# STM32_microcontroller_IOs.net
KiCad netlist of a schematic drawn in Altium Designer
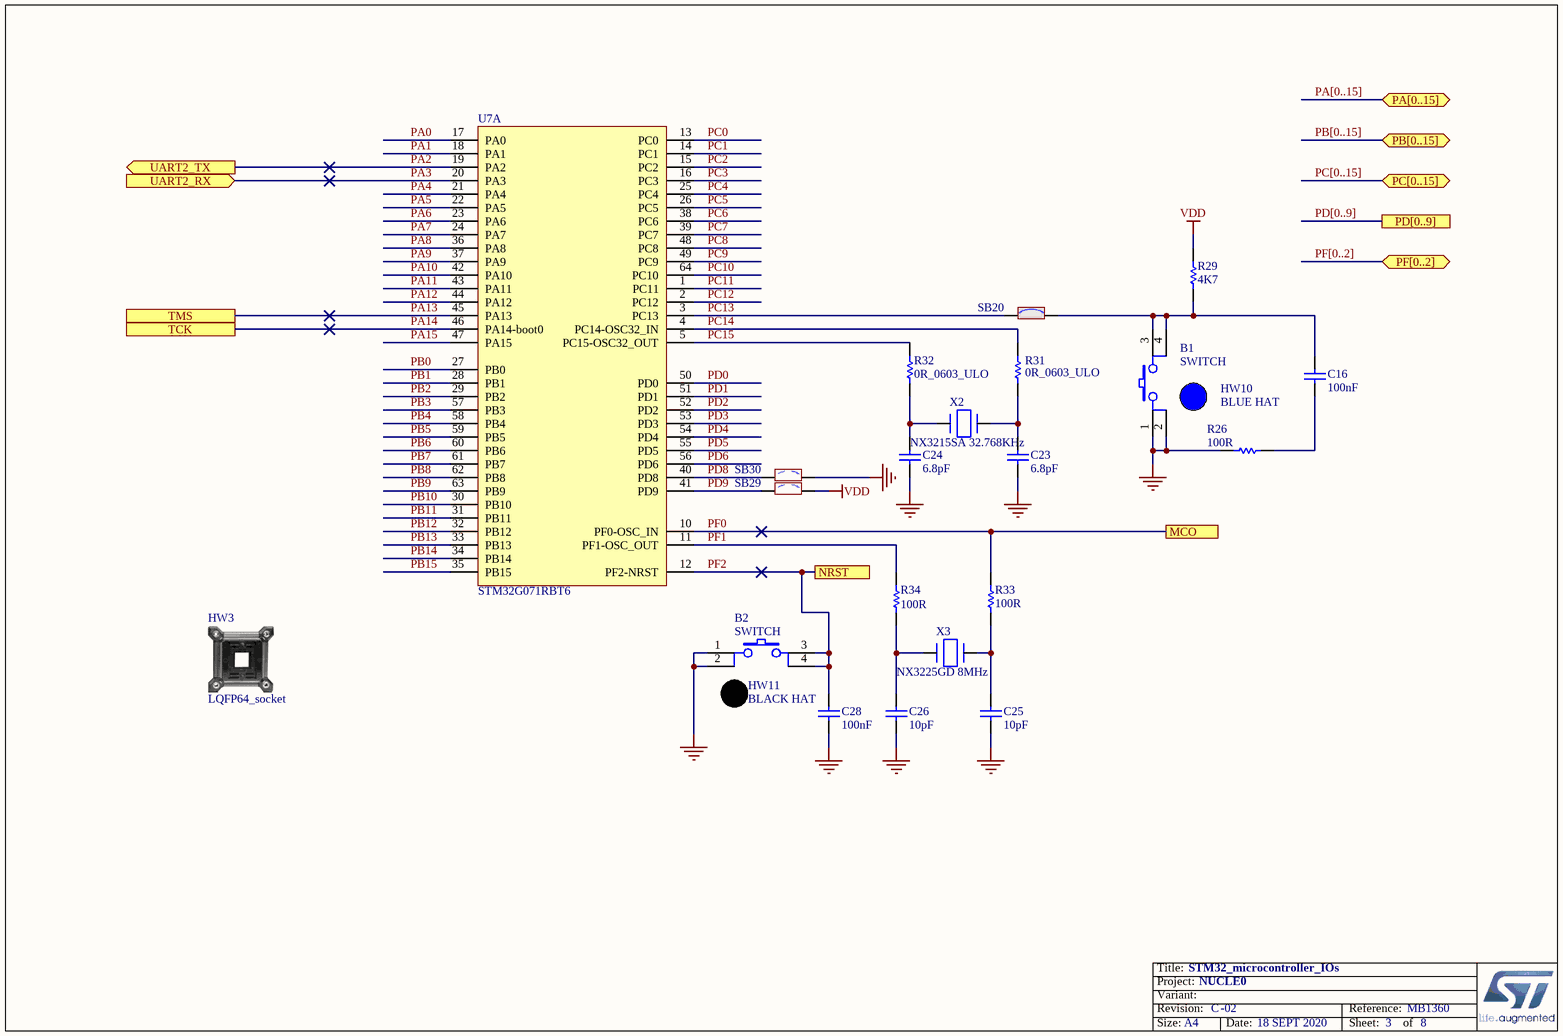
[diagram p0: STM32_microcontroller_IOs.SchDoc]

(export (version "E")
  (design (tool "Eeschema 10.0.6"))
  (components
    (comp (ref "B1")
      (value "SWITCH")
      (footprint "SWI_WEALTHMETAL_TD-0341_4P_BLUE")
      (description "Non-Open Push-Button 0.1A 24V")
      (fields
        (field (name "INTERNAL_PART_NUMBER") "MCD-00002")
        (field (name "MANUFACTURER_PART_NUMBER") "TD-0341")
        (field (name "PROVIDED_BY") "SUBCO")
      )
      (libsource (lib "MCD_PARTS_database") (part "SW-PUSH-CMS"))
    )
    (comp (ref "B2")
      (value "SWITCH")
      (footprint "SWI_WEALTHMETAL_TD-0341_4P_BLACK")
      (description "Non-Open Push-Button 0.1A 24V BLACK")
      (fields
        (field (name "INTERNAL_PART_NUMBER") "MCD-00001")
        (field (name "MANUFACTURER_PART_NUMBER") "TD-0341")
        (field (name "PROVIDED_BY") "SUBCO")
      )
      (libsource (lib "MCD_PARTS_database") (part "SW-PUSH-CMS"))
    )
    (comp (ref "C16")
      (value "100nF")
      (footprint "C0603")
      (description "Capacitor, MLCC, 100nF, 16V, X7R, 10%, 0603, T=0,8mm")
      (fields
        (field (name "INTERNAL_PART_NUMBER") "MCD-00211")
        (field (name "MANUFACTURER_PART_NUMBER") "CC0603KRX7R7BB104")
        (field (name "PROVIDED_BY") "SUBCO")
      )
      (libsource (lib "MCD_PARTS_database") (part "Capacitor"))
    )
    (comp (ref "C23")
      (value "6.8pF")
      (footprint "C0603")
      (description "Capacitor, MLCC, 6.8pF, 50V, NPO, -/+0.25pF, 0603, T=0,8mm")
      (fields (field (name "INTERNAL_PART_NUMBER") "MCD-00650") (field (name "MANUFACTURER") "YAGEO"))
      (libsource (lib "MCD_PARTS_database") (part "Capacitor"))
    )
    (comp (ref "C24")
      (value "6.8pF")
      (footprint "C0603")
      (description "Capacitor, MLCC, 6.8pF, 50V, NPO, -/+0.25pF, 0603, T=0,8mm")
      (fields (field (name "INTERNAL_PART_NUMBER") "MCD-00650") (field (name "MANUFACTURER") "YAGEO"))
      (libsource (lib "MCD_PARTS_database") (part "Capacitor"))
    )
    (comp (ref "C25")
      (value "10pF")
      (footprint "C0603")
      (description "Capacitor, MLCC, 10pF, 50V, NPO, 5%, 0603, T=0,8mm")
      (fields
        (field (name "INTERNAL_PART_NUMBER") "MCD-00637")
        (field (name "MANUFACTURER_PART_NUMBER") "CC0603JRNPO9BN100")
        (field (name "PROVIDED_BY") "SUBCO")
      )
      (libsource (lib "MCD_PARTS_database") (part "Capacitor"))
    )
    (comp (ref "C26")
      (value "10pF")
      (footprint "C0603")
      (description "Capacitor, MLCC, 10pF, 50V, NPO, 5%, 0603, T=0,8mm")
      (fields
        (field (name "INTERNAL_PART_NUMBER") "MCD-00637")
        (field (name "MANUFACTURER_PART_NUMBER") "CC0603JRNPO9BN100")
        (field (name "PROVIDED_BY") "SUBCO")
      )
      (libsource (lib "MCD_PARTS_database") (part "Capacitor"))
    )
    (comp (ref "C28")
      (value "100nF")
      (footprint "C0603")
      (description "Capacitor, MLCC, 100nF, 16V, X7R, 10%, 0603, T=0,8mm")
      (fields
        (field (name "INTERNAL_PART_NUMBER") "MCD-00211")
        (field (name "MANUFACTURER_PART_NUMBER") "CC0603KRX7R7BB104")
        (field (name "PROVIDED_BY") "SUBCO")
      )
      (libsource (lib "MCD_PARTS_database") (part "Capacitor"))
    )
    (comp (ref "HW3")
      (value "LQFP64_socket")
      (description "Yamaichi socket for LQFP64, with positioning pins.")
      (fields
        (field (name "INTERNAL_PART_NUMBER") "MCD-01253")
        (field (name "MANUFACTURER_PART_NUMBER") "IC149-064-169-B5")
        (field (name "PROVIDED_BY") "SUBCO")
      )
      (libsource (lib "MCD_PARTS_database") (part "SOCKET_LQFP64"))
    )
    (comp (ref "HW10")
      (value "BLUE HAT")
      (description "Blue Hat for switch TD0341X-G01-BLU")
      (fields
        (field (name "INTERNAL_PART_NUMBER") "MCD-00634")
        (field (name "MANUFACTURER_PART_NUMBER") "988.16.09.3.00002_SH-517")
        (field (name "PROVIDED_BY") "SUBCO")
      )
      (libsource (lib "MCD_PARTS_database") (part "BUTTON_HAT_BLUE"))
    )
    (comp (ref "HW11")
      (value "BLACK HAT")
      (description "Black Hat for switch TD0341X-G01-BLA")
      (fields
        (field (name "INTERNAL_PART_NUMBER") "MCD-00635")
        (field (name "MANUFACTURER_PART_NUMBER") "988.16.09.3.00003_SH-517")
        (field (name "PROVIDED_BY") "SUBCO")
      )
      (libsource (lib "MCD_PARTS_database") (part "BUTTON_HAT_BLACK"))
    )
    (comp (ref "R26")
      (value "100R")
      (footprint "R0603")
      (description "Resistor,100R,0603,1%,1/10W")
      (fields
        (field (name "INTERNAL_PART_NUMBER") "MCD-00224")
        (field (name "MANUFACTURER_PART_NUMBER") "RC0603FR-07100RL")
        (field (name "PROVIDED_BY") "SUBCO")
      )
      (libsource (lib "MCD_PARTS_database") (part "Resistor"))
    )
    (comp (ref "R29")
      (value "4K7")
      (footprint "R0603")
      (description "Resistor,4K7,0603,1%,1/10W")
      (fields
        (field (name "INTERNAL_PART_NUMBER") "MCD-00219")
        (field (name "MANUFACTURER_PART_NUMBER") "RC0603FR-074K7L")
        (field (name "PROVIDED_BY") "SUBCO")
      )
      (libsource (lib "MCD_PARTS_database") (part "Resistor"))
    )
    (comp (ref "R31")
      (value "0R_0603_ULO")
      (footprint "R0603")
      (description "Resistor,0R,0603,ULO")
      (fields
        (field (name "INTERNAL_PART_NUMBER") "MCD-00181")
        (field (name "MANUFACTURER_PART_NUMBER") "PMR03EZPJ000")
        (field (name "PROVIDED_BY") "SUBCO")
      )
      (libsource (lib "MCD_PARTS_database") (part "Resistor"))
    )
    (comp (ref "R32")
      (value "0R_0603_ULO")
      (footprint "R0603")
      (description "Resistor,0R,0603,ULO")
      (fields
        (field (name "INTERNAL_PART_NUMBER") "MCD-00181")
        (field (name "MANUFACTURER_PART_NUMBER") "PMR03EZPJ000")
        (field (name "PROVIDED_BY") "SUBCO")
      )
      (libsource (lib "MCD_PARTS_database") (part "Resistor"))
    )
    (comp (ref "R33")
      (value "100R")
      (footprint "R0603")
      (description "Resistor,100R,0603,1%,1/10W")
      (fields
        (field (name "INTERNAL_PART_NUMBER") "MCD-00224")
        (field (name "MANUFACTURER_PART_NUMBER") "RC0603FR-07100RL")
        (field (name "PROVIDED_BY") "SUBCO")
      )
      (libsource (lib "MCD_PARTS_database") (part "Resistor"))
    )
    (comp (ref "R34")
      (value "100R")
      (footprint "R0603")
      (description "Resistor,100R,0603,1%,1/10W")
      (fields
        (field (name "INTERNAL_PART_NUMBER") "MCD-00224")
        (field (name "MANUFACTURER_PART_NUMBER") "RC0603FR-07100RL")
        (field (name "PROVIDED_BY") "SUBCO")
      )
      (libsource (lib "MCD_PARTS_database") (part "Resistor"))
    )
    (comp (ref "SB20")
      (value "SB_ON")
      (footprint "SOLDER-BRIDGE_R0603-0R")
      (description "Solder Bridge ON")
      (fields
        (field (name "INTERNAL_PART_NUMBER") "MCD-00071")
        (field (name "MANUFACTURER_PART_NUMBER") "RC0603JR-070RL")
        (field (name "PROVIDED_BY") "SUBCO")
      )
      (libsource (lib "MCD_PARTS_database") (part "SB_ON"))
    )
    (comp (ref "SB29")
      (value "SB_OFF")
      (footprint "SOLDER-BRIDGE_R0603-0R")
      (description "Solder Bridge OFF")
      (fields
        (field (name "INTERNAL_PART_NUMBER") "MCD-00072")
        (field (name "MANUFACTURER_PART_NUMBER") "RC0603JR-070RL")
        (field (name "PROVIDED_BY") "SUBCO")
      )
      (libsource (lib "MCD_PARTS_database") (part "SB_OFF"))
    )
    (comp (ref "SB30")
      (value "SB_OFF")
      (footprint "SOLDER-BRIDGE_R0603-0R")
      (description "Solder Bridge OFF")
      (fields
        (field (name "INTERNAL_PART_NUMBER") "MCD-00072")
        (field (name "MANUFACTURER_PART_NUMBER") "RC0603JR-070RL")
        (field (name "PROVIDED_BY") "SUBCO")
      )
      (libsource (lib "MCD_PARTS_database") (part "SB_OFF"))
    )
    (comp (ref "U7")
      (value "STM32G071RBT6")
      (footprint "ICC_LQFP64_10X10_P050_SOCKET_YAMAICHI_IC149-064-069-B5")
      (fields
        (field (name "INTERNAL_PART_NUMBER") "MCD-00662")
        (field (name "MANUFACTURER") "STMICROELECTRONICS")
        (field (name "BMS_PART_NUMBER") "9175318")
        (field (name "PROVIDED_BY") "SUBCO with ST control")
      )
      (libsource (lib "MCD_PARTS_database") (part "STM32G071RBT6"))
    )
    (comp (ref "X2")
      (value "NX3215SA 32.768KHz")
      (footprint "CRY_NX3215SA_2P")
      (description "Crystal 32.768kHz, 6pF, +-20ppm, 50Kohms max, SMD")
      (fields
        (field (name "INTERNAL_PART_NUMBER") "MCD-00091")
        (field (name "MANUFACTURER_PART_NUMBER") "NX3215SA 32.768KHz EXS00A-MU00525")
        (field (name "PROVIDED_BY") "SUBCO")
      )
      (libsource (lib "MCD_PARTS_database") (part "XTAL_2_PINS"))
    )
    (comp (ref "X3")
      (value "NX3225GD 8MHz")
      (footprint "CRY_NX3225GD_2P")
      (description "Crystal 8MHz, 8pF, +-20ppm, 500ohms max,  SMD")
      (fields
        (field (name "INTERNAL_PART_NUMBER") "MCD-00092")
        (field (name "MANUFACTURER_PART_NUMBER") "NX3225GD 8MHz EXS00A-CG04874")
        (field (name "PROVIDED_BY") "SUBCO")
      )
      (libsource (lib "MCD_PARTS_database") (part "XTAL_2_PINS"))
    )
  )
  (nets
    (net (code "2") (name "/PA0") (class "Default")
      (node (ref "U7") (pin "17") (pinfunction "PA0_17") (pintype "passive"))
    )
    (net (code "3") (name "/PA1") (class "Default")
      (node (ref "U7") (pin "18") (pinfunction "PA1_18") (pintype "passive"))
    )
    (net (code "4") (name "/PA2") (class "Default")
      (node (ref "U7") (pin "19") (pinfunction "PA2_19") (pintype "passive"))
    )
    (net (code "5") (name "/PA3") (class "Default")
      (node (ref "U7") (pin "20") (pinfunction "PA3_20") (pintype "passive"))
    )
    (net (code "6") (name "/PA4") (class "Default")
      (node (ref "U7") (pin "21") (pinfunction "PA4_21") (pintype "passive"))
    )
    (net (code "7") (name "/PA5") (class "Default")
      (node (ref "U7") (pin "22") (pinfunction "PA5_22") (pintype "passive"))
    )
    (net (code "8") (name "/PA6") (class "Default")
      (node (ref "U7") (pin "23") (pinfunction "PA6_23") (pintype "passive"))
    )
    (net (code "9") (name "/PA7") (class "Default")
      (node (ref "U7") (pin "24") (pinfunction "PA7_24") (pintype "passive"))
    )
    (net (code "10") (name "/PA8") (class "Default")
      (node (ref "U7") (pin "36") (pinfunction "PA8_36") (pintype "passive"))
    )
    (net (code "11") (name "/PA9") (class "Default")
      (node (ref "U7") (pin "37") (pinfunction "PA9_37") (pintype "passive"))
    )
    (net (code "12") (name "/PA10") (class "Default")
      (node (ref "U7") (pin "42") (pinfunction "PA10_42") (pintype "passive"))
    )
    (net (code "13") (name "/PA11") (class "Default")
      (node (ref "U7") (pin "43") (pinfunction "PA11_43") (pintype "passive"))
    )
    (net (code "14") (name "/PA12") (class "Default")
      (node (ref "U7") (pin "44") (pinfunction "PA12_44") (pintype "passive"))
    )
    (net (code "15") (name "/PA13") (class "Default")
      (node (ref "U7") (pin "45") (pinfunction "PA13_45") (pintype "passive"))
    )
    (net (code "16") (name "/PA14") (class "Default")
      (node (ref "U7") (pin "46") (pinfunction "PA14-boot0_46") (pintype "passive"))
    )
    (net (code "17") (name "/PA15") (class "Default")
      (node (ref "U7") (pin "47") (pinfunction "PA15_47") (pintype "passive"))
    )
    (net (code "19") (name "/PB0") (class "Default")
      (node (ref "U7") (pin "27") (pinfunction "PB0_27") (pintype "passive"))
    )
    (net (code "20") (name "/PB1") (class "Default")
      (node (ref "U7") (pin "28") (pinfunction "PB1_28") (pintype "passive"))
    )
    (net (code "21") (name "/PB2") (class "Default")
      (node (ref "U7") (pin "29") (pinfunction "PB2_29") (pintype "passive"))
    )
    (net (code "22") (name "/PB3") (class "Default")
      (node (ref "U7") (pin "57") (pinfunction "PB3_57") (pintype "passive"))
    )
    (net (code "23") (name "/PB4") (class "Default")
      (node (ref "U7") (pin "58") (pinfunction "PB4_58") (pintype "passive"))
    )
    (net (code "24") (name "/PB5") (class "Default")
      (node (ref "U7") (pin "59") (pinfunction "PB5_59") (pintype "passive"))
    )
    (net (code "25") (name "/PB6") (class "Default")
      (node (ref "U7") (pin "60") (pinfunction "PB6_60") (pintype "passive"))
    )
    (net (code "26") (name "/PB7") (class "Default")
      (node (ref "U7") (pin "61") (pinfunction "PB7_61") (pintype "passive"))
    )
    (net (code "27") (name "/PB8") (class "Default")
      (node (ref "U7") (pin "62") (pinfunction "PB8_62") (pintype "passive"))
    )
    (net (code "28") (name "/PB9") (class "Default")
      (node (ref "U7") (pin "63") (pinfunction "PB9_63") (pintype "passive"))
    )
    (net (code "29") (name "/PB10") (class "Default")
      (node (ref "U7") (pin "30") (pinfunction "PB10_30") (pintype "passive"))
    )
    (net (code "30") (name "/PB11") (class "Default")
      (node (ref "U7") (pin "31") (pinfunction "PB11_31") (pintype "passive"))
    )
    (net (code "31") (name "/PB12") (class "Default")
      (node (ref "U7") (pin "32") (pinfunction "PB12_32") (pintype "passive"))
    )
    (net (code "32") (name "/PB13") (class "Default")
      (node (ref "U7") (pin "33") (pinfunction "PB13_33") (pintype "passive"))
    )
    (net (code "33") (name "/PB14") (class "Default")
      (node (ref "U7") (pin "34") (pinfunction "PB14_34") (pintype "passive"))
    )
    (net (code "34") (name "/PB15") (class "Default")
      (node (ref "U7") (pin "35") (pinfunction "PB15_35") (pintype "passive"))
    )
    (net (code "36") (name "/PC0") (class "Default")
      (node (ref "U7") (pin "13") (pinfunction "PC0_13") (pintype "passive"))
    )
    (net (code "37") (name "/PC1") (class "Default")
      (node (ref "U7") (pin "14") (pinfunction "PC1_14") (pintype "passive"))
    )
    (net (code "38") (name "/PC2") (class "Default")
      (node (ref "U7") (pin "15") (pinfunction "PC2_15") (pintype "passive"))
    )
    (net (code "39") (name "/PC3") (class "Default")
      (node (ref "U7") (pin "16") (pinfunction "PC3_16") (pintype "passive"))
    )
    (net (code "40") (name "/PC4") (class "Default")
      (node (ref "U7") (pin "25") (pinfunction "PC4_25") (pintype "passive"))
    )
    (net (code "41") (name "/PC5") (class "Default")
      (node (ref "U7") (pin "26") (pinfunction "PC5_26") (pintype "passive"))
    )
    (net (code "42") (name "/PC6") (class "Default")
      (node (ref "U7") (pin "38") (pinfunction "PC6_38") (pintype "passive"))
    )
    (net (code "43") (name "/PC7") (class "Default")
      (node (ref "U7") (pin "39") (pinfunction "PC7_39") (pintype "passive"))
    )
    (net (code "44") (name "/PC8") (class "Default")
      (node (ref "U7") (pin "48") (pinfunction "PC8_48") (pintype "passive"))
    )
    (net (code "45") (name "/PC9") (class "Default")
      (node (ref "U7") (pin "49") (pinfunction "PC9_49") (pintype "passive"))
    )
    (net (code "46") (name "/PC10") (class "Default")
      (node (ref "U7") (pin "64") (pinfunction "PC10_64") (pintype "passive"))
    )
    (net (code "47") (name "/PC11") (class "Default")
      (node (ref "U7") (pin "1") (pinfunction "PC11_1") (pintype "passive"))
    )
    (net (code "48") (name "/PC12") (class "Default")
      (node (ref "U7") (pin "2") (pinfunction "PC12_2") (pintype "passive"))
    )
    (net (code "49") (name "/PC13") (class "Default")
      (node (ref "SB20") (pin "1") (pinfunction "1_1") (pintype "passive"))
      (node (ref "U7") (pin "3") (pinfunction "PC13_3") (pintype "passive"))
    )
    (net (code "50") (name "/PC14") (class "Default")
      (node (ref "R31") (pin "1") (pinfunction "1_1") (pintype "passive"))
      (node (ref "U7") (pin "4") (pinfunction "PC14-OSC32_IN_4") (pintype "passive"))
    )
    (net (code "51") (name "/PC15") (class "Default")
      (node (ref "R32") (pin "1") (pinfunction "1_1") (pintype "passive"))
      (node (ref "U7") (pin "5") (pinfunction "PC15-OSC32_OUT_5") (pintype "passive"))
    )
    (net (code "53") (name "/PD0") (class "Default")
      (node (ref "U7") (pin "50") (pinfunction "PD0_50") (pintype "passive"))
    )
    (net (code "54") (name "/PD1") (class "Default")
      (node (ref "U7") (pin "51") (pinfunction "PD1_51") (pintype "passive"))
    )
    (net (code "55") (name "/PD2") (class "Default")
      (node (ref "U7") (pin "52") (pinfunction "PD2_52") (pintype "passive"))
    )
    (net (code "56") (name "/PD3") (class "Default")
      (node (ref "U7") (pin "53") (pinfunction "PD3_53") (pintype "passive"))
    )
    (net (code "57") (name "/PD4") (class "Default")
      (node (ref "U7") (pin "54") (pinfunction "PD4_54") (pintype "passive"))
    )
    (net (code "58") (name "/PD5") (class "Default")
      (node (ref "U7") (pin "55") (pinfunction "PD5_55") (pintype "passive"))
    )
    (net (code "59") (name "/PD6") (class "Default")
      (node (ref "U7") (pin "56") (pinfunction "PD6_56") (pintype "passive"))
    )
    (net (code "60") (name "/PD8") (class "Default")
      (node (ref "SB30") (pin "1") (pinfunction "1_1") (pintype "passive"))
      (node (ref "U7") (pin "40") (pinfunction "PD8_40") (pintype "passive"))
    )
    (net (code "61") (name "/PD9") (class "Default")
      (node (ref "SB29") (pin "1") (pinfunction "1_1") (pintype "passive"))
      (node (ref "U7") (pin "41") (pinfunction "PD9_41") (pintype "passive"))
    )
    (net (code "63") (name "/PF0") (class "Default")
      (node (ref "R33") (pin "1") (pinfunction "1_1") (pintype "passive"))
      (node (ref "U7") (pin "10") (pinfunction "PF0-OSC_IN_10") (pintype "passive"))
    )
    (net (code "64") (name "/PF1") (class "Default")
      (node (ref "R34") (pin "1") (pinfunction "1_1") (pintype "passive"))
      (node (ref "U7") (pin "11") (pinfunction "PF1-OSC_OUT_11") (pintype "passive"))
    )
    (net (code "65") (name "/PF2") (class "Default")
      (node (ref "B2") (pin "3") (pinfunction "3_3") (pintype "passive"))
      (node (ref "B2") (pin "4") (pinfunction "4_4") (pintype "passive"))
      (node (ref "C28") (pin "2") (pinfunction "2_2") (pintype "passive"))
      (node (ref "U7") (pin "12") (pinfunction "PF2-NRST_12") (pintype "passive"))
    )
    (net (code "67") (name "GND") (class "Default")
      (node (ref "B1") (pin "1") (pinfunction "1_1") (pintype "passive"))
      (node (ref "B1") (pin "2") (pinfunction "2_2") (pintype "passive"))
      (node (ref "B2") (pin "1") (pinfunction "1_1") (pintype "passive"))
      (node (ref "B2") (pin "2") (pinfunction "2_2") (pintype "passive"))
      (node (ref "C23") (pin "1") (pinfunction "1_1") (pintype "passive"))
      (node (ref "C24") (pin "1") (pinfunction "1_1") (pintype "passive"))
      (node (ref "C25") (pin "1") (pinfunction "1_1") (pintype "passive"))
      (node (ref "C26") (pin "1") (pinfunction "1_1") (pintype "passive"))
      (node (ref "C28") (pin "1") (pinfunction "1_1") (pintype "passive"))
      (node (ref "R26") (pin "1") (pinfunction "1_1") (pintype "passive"))
      (node (ref "SB30") (pin "2") (pinfunction "2_2") (pintype "passive"))
    )
    (net (code "68") (name "Net-(B1-Pad3)") (class "Default")
      (node (ref "B1") (pin "3") (pinfunction "3_3") (pintype "passive"))
      (node (ref "B1") (pin "4") (pinfunction "4_4") (pintype "passive"))
      (node (ref "C16") (pin "2") (pinfunction "2_2") (pintype "passive"))
      (node (ref "R29") (pin "1") (pinfunction "1_1") (pintype "passive"))
      (node (ref "SB20") (pin "2") (pinfunction "2_2") (pintype "passive"))
    )
    (net (code "69") (name "Net-(C16-Pad1)") (class "Default")
      (node (ref "C16") (pin "1") (pinfunction "1_1") (pintype "passive"))
      (node (ref "R26") (pin "2") (pinfunction "2_2") (pintype "passive"))
    )
    (net (code "70") (name "Net-(X2-X1)") (class "Default")
      (node (ref "C24") (pin "2") (pinfunction "2_2") (pintype "passive"))
      (node (ref "R32") (pin "2") (pinfunction "2_2") (pintype "passive"))
      (node (ref "X2") (pin "1") (pinfunction "X1_1") (pintype "passive"))
    )
    (net (code "71") (name "Net-(X2-X2)") (class "Default")
      (node (ref "C23") (pin "2") (pinfunction "2_2") (pintype "passive"))
      (node (ref "R31") (pin "2") (pinfunction "2_2") (pintype "passive"))
      (node (ref "X2") (pin "2") (pinfunction "X2_2") (pintype "passive"))
    )
    (net (code "72") (name "Net-(X3-X1)") (class "Default")
      (node (ref "C26") (pin "2") (pinfunction "2_2") (pintype "passive"))
      (node (ref "R34") (pin "2") (pinfunction "2_2") (pintype "passive"))
      (node (ref "X3") (pin "1") (pinfunction "X1_1") (pintype "passive"))
    )
    (net (code "73") (name "Net-(X3-X2)") (class "Default")
      (node (ref "C25") (pin "2") (pinfunction "2_2") (pintype "passive"))
      (node (ref "R33") (pin "2") (pinfunction "2_2") (pintype "passive"))
      (node (ref "X3") (pin "2") (pinfunction "X2_2") (pintype "passive"))
    )
    (net (code "74") (name "VDD") (class "Default")
      (node (ref "R29") (pin "2") (pinfunction "2_2") (pintype "passive"))
      (node (ref "SB29") (pin "2") (pinfunction "2_2") (pintype "passive"))
    )
  )
)
